# JacdacButton_10.net
KiCad netlist of a schematic drawn in Altium Designer
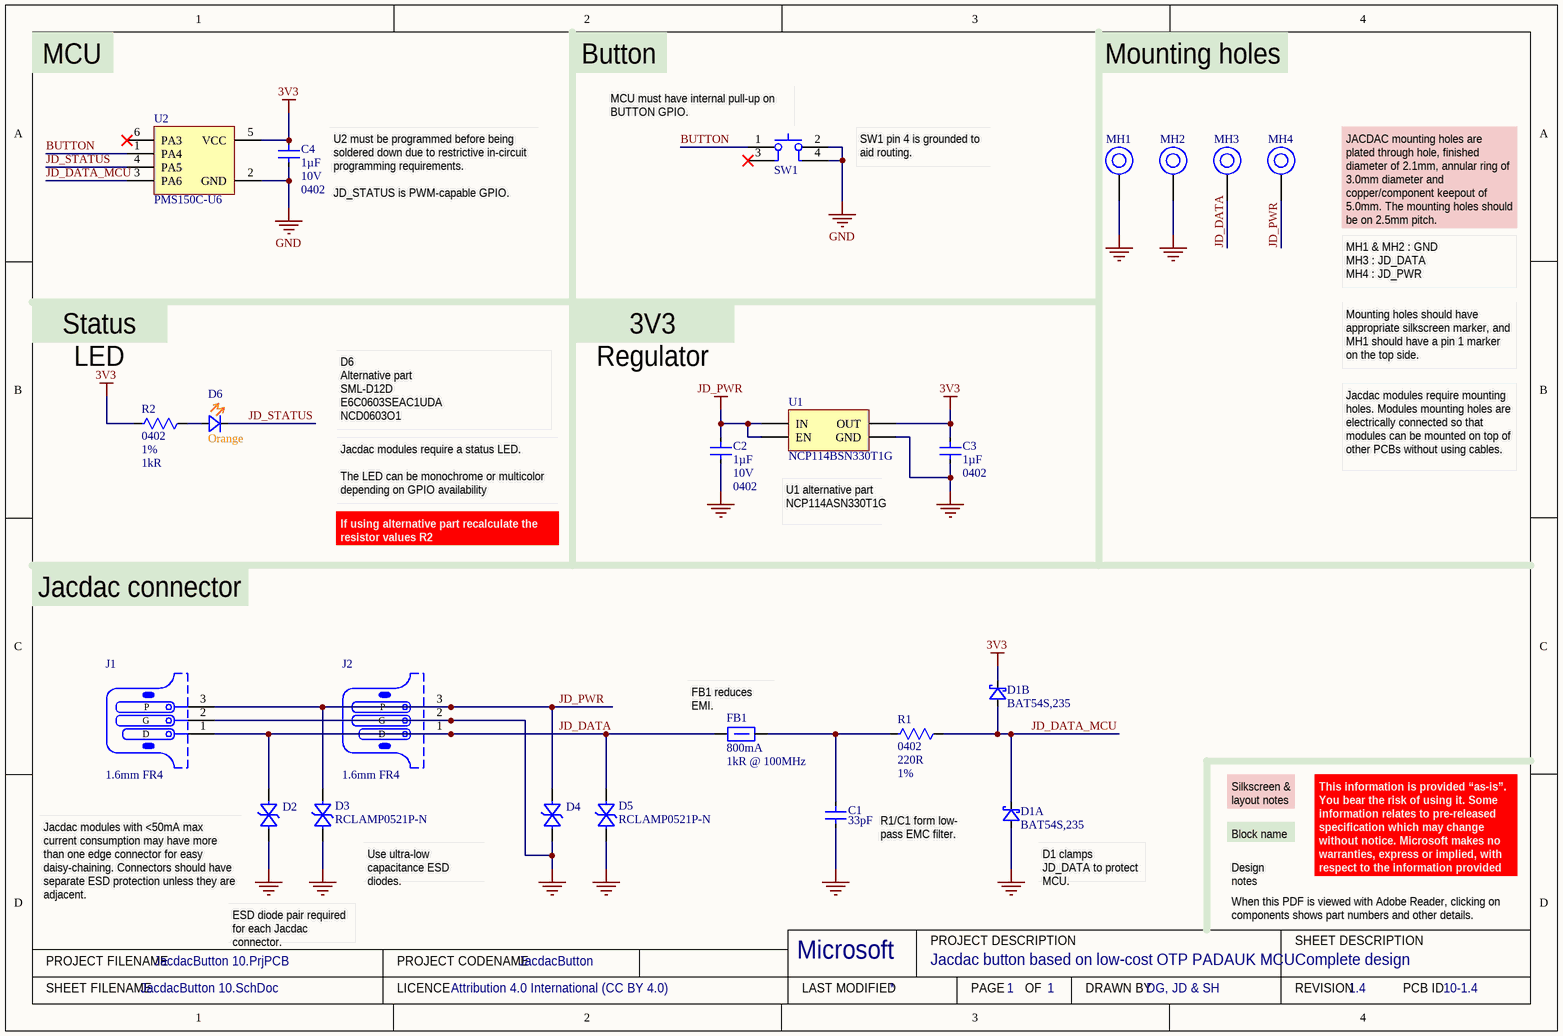
[diagram p0: JacdacButton 10.SchDoc]

(export (version "E")
  (design (tool "Eeschema 10.0.6"))
  (components
    (comp (ref "C1")
      (value "CL05C330JB5NNNC")
      (footprint "C0402_0.55MM - without outline")
      (description "CAP CER 33PF 50V C0G/NP0 0402")
      (fields
        (field (name "MANUFACTURER") "Samsung")
        (field (name "TOLERANCE") "5%")
        (field (name "CAPACITANCE") "33pF")
      )
      (libsource (lib "Samsung") (part "CL05C330JB5NNNC"))
    )
    (comp (ref "C2")
      (value "CL05A105KP5NNNC")
      (footprint "C0402_0.55MM - without outline")
      (description "CAP CER 1UF 10V X5R 0402")
      (fields
        (field (name "MANUFACTURER") "Samsung")
        (field (name "TOLERANCE") "10%")
        (field (name "CAPACITANCE") "1µF")
        (field (name "VOLTAGE RATING") "10V")
        (field (name "CASE CODE (IMPERIAL)") "0402")
        (field (name "CREATED") "DG")
        (field (name "CHECKED") "?")
      )
      (libsource (lib "Samsung") (part "CL05A105KP5NNNC"))
    )
    (comp (ref "C3")
      (value "CL05A105KP5NNNC")
      (footprint "C0402_0.55MM - without outline")
      (description "CAP CER 1UF 10V X5R 0402")
      (fields
        (field (name "MANUFACTURER") "Samsung")
        (field (name "TOLERANCE") "10%")
        (field (name "CAPACITANCE") "1µF")
        (field (name "CASE CODE (IMPERIAL)") "0402")
        (field (name "CREATED") "DG")
        (field (name "CHECKED") "?")
      )
      (libsource (lib "Samsung") (part "CL05A105KP5NNNC"))
    )
    (comp (ref "C4")
      (value "CL05A105KP5NNNC")
      (footprint "C0402_0.55MM - without outline")
      (description "CAP CER 1UF 10V X5R 0402")
      (fields
        (field (name "MANUFACTURER") "Samsung")
        (field (name "TOLERANCE") "10%")
        (field (name "CAPACITANCE") "1µF")
        (field (name "VOLTAGE RATING") "10V")
        (field (name "CASE CODE (IMPERIAL)") "0402")
        (field (name "CREATED") "DG")
        (field (name "CHECKED") "?")
      )
      (libsource (lib "Samsung") (part "CL05A105KP5NNNC"))
    )
    (comp (ref "D1")
      (value "BAT54S")
      (footprint "NXP-BAT54S-TO-236AB - without outline")
      (description "DIODE ARRAY SCHOTTKY 30V SOT23")
      (fields (field (name "MANUFACTURER") "Nexperia") (field (name "MANUFACTURER PART NUMBER") "BAT54S,235"))
      (libsource (lib "NXP") (part "BAT54S"))
    )
    (comp (ref "D2")
      (value "RCLAMP0521P-N")
      (footprint "TVS 0402 - L")
      (description "Bidirectional 5V (Max) 6V 16V 3.5A (8/20us) 0402 TVS RoHS")
      (fields
        (field (name "MANUFACTURER") "Born Semiconductor")
        (field (name "CREATED BY") "D Gakure")
        (field (name "CHECKED BY") "?")
      )
      (libsource (lib "BornSemiconductor") (part "RCLAMP0521P-N"))
    )
    (comp (ref "D3")
      (value "RCLAMP0521P-N")
      (footprint "TVS 0402 - L")
      (description "Bidirectional 5V (Max) 6V 16V 3.5A (8/20us) 0402 TVS RoHS")
      (fields
        (field (name "MANUFACTURER") "Born Semiconductor")
        (field (name "MANUFACTURER PART NUMBER") "RCLAMP0521P-N")
        (field (name "CREATED BY") "D Gakure")
        (field (name "CHECKED BY") "?")
      )
      (libsource (lib "BornSemiconductor") (part "RCLAMP0521P-N"))
    )
    (comp (ref "D4")
      (value "RCLAMP0521P-N")
      (footprint "TVS 0402 - L")
      (description "Bidirectional 5V (Max) 6V 16V 3.5A (8/20us) 0402 TVS RoHS")
      (fields
        (field (name "MANUFACTURER") "Born Semiconductor")
        (field (name "CREATED BY") "D Gakure")
        (field (name "CHECKED BY") "?")
      )
      (libsource (lib "BornSemiconductor") (part "RCLAMP0521P-N"))
    )
    (comp (ref "D5")
      (value "RCLAMP0521P-N")
      (footprint "TVS 0402 - L")
      (description "Bidirectional 5V (Max) 6V 16V 3.5A (8/20us) 0402 TVS RoHS")
      (fields
        (field (name "MANUFACTURER") "Born Semiconductor")
        (field (name "MANUFACTURER PART NUMBER") "RCLAMP0521P-N")
        (field (name "CREATED BY") "D Gakure")
        (field (name "CHECKED BY") "?")
      )
      (libsource (lib "BornSemiconductor") (part "RCLAMP0521P-N"))
    )
    (comp (ref "D6")
      (value "~")
      (footprint "0603 Orange - without outline")
      (description "LED ORANGE DIFFUSED 1608 SMD")
      (fields
        (field (name "MANUFACTURER") "Everlight Elec")
        (field (name "MANUFACTURER PART NUMBER") "19-217/S2C-AQ1R1B/3T")
        (field (name "COLOUR") "Orange")
      )
      (libsource (lib "EverlightElec") (part "19-217/S2C-AQ1R1B/3T"))
    )
    (comp (ref "FB1")
      (value "TDK MPZ1608S102ATA00")
      (footprint "TDK MPZ1608 0.8mm - without outline")
      (description "0603 1k@100MHz 0.8A chip")
      (fields
        (field (name "TOLERANCE") "25%")
        (field (name "MANUFACTURER") "TDK")
        (field (name "CURRENT RATING") "800mA")
        (field (name "IMPEDANCE") "1kR @ 100MHz")
      )
      (libsource (lib "TDK") (part "TDK MPZ1608S102ATA00"))
    )
    (comp (ref "J1")
      (value "3 pin JACDAC edge connector")
      (footprint "JACDAC_EDGE_CONNECTOR_NO_TRACES")
      (description "3 pin Jacdac edge connector 1.27mm pitch")
      (fields
        (field (name "MANUFACTURER PART NUMBER") "JACDAC_EDGE_CONNECTOR")
        (field (name "PCB TYPE") "1.6mm FR4")
        (field (name "CHECKED BY") "?")
        (field (name "CREATED BY") "D. Gakure")
      )
      (libsource (lib "generic-con") (part "Jacdac edge connector"))
    )
    (comp (ref "J2")
      (value "3 pin JACDAC edge connector")
      (footprint "JACDAC_EDGE_CONNECTOR_NO_TRACES")
      (description "3 pin Jacdac edge connector 1.27mm pitch")
      (fields
        (field (name "MANUFACTURER PART NUMBER") "JACDAC_EDGE_CONNECTOR")
        (field (name "PCB TYPE") "1.6mm FR4")
        (field (name "CHECKED BY") "?")
        (field (name "CREATED BY") "D. Gakure")
      )
      (libsource (lib "generic-con") (part "Jacdac edge connector"))
    )
    (comp (ref "MH1")
      (value "MH_5.0MMK_3.0MMC_2.1MMD_PTH")
      (footprint "MH_5.0MMK_3.0MMC_2.1MMD_PTH")
      (description "Mounting Hole 5.0mm keepout, 3.0mm annualar ring and 2.1mm Drill PTH")
      (libsource (lib "generic") (part "MH_5.0MMK_3.0MMC_2.1MMD_PTH"))
    )
    (comp (ref "MH2")
      (value "MH_5.0MMK_3.0MMC_2.1MMD_PTH")
      (footprint "MH_5.0MMK_3.0MMC_2.1MMD_PTH")
      (description "Mounting Hole 5.0mm keepout, 3.0mm annualar ring and 2.1mm Drill PTH")
      (libsource (lib "generic") (part "MH_5.0MMK_3.0MMC_2.1MMD_PTH"))
    )
    (comp (ref "MH3")
      (value "MH_5.0MMK_3.0MMC_2.1MMD_PTH")
      (footprint "MH_5.0MMK_3.0MMC_2.1MMD_PTH")
      (description "Mounting Hole 5.0mm keepout, 3.0mm annualar ring and 2.1mm Drill PTH")
      (libsource (lib "generic") (part "MH_5.0MMK_3.0MMC_2.1MMD_PTH"))
    )
    (comp (ref "MH4")
      (value "MH_5.0MMK_3.0MMC_2.1MMD_PTH")
      (footprint "MH_5.0MMK_3.0MMC_2.1MMD_PTH")
      (description "Mounting Hole 5.0mm keepout, 3.0mm annualar ring and 2.1mm Drill PTH")
      (libsource (lib "generic") (part "MH_5.0MMK_3.0MMC_2.1MMD_PTH"))
    )
    (comp (ref "R1")
      (value "RC0402FR-07220RL")
      (footprint "R0402 - Without outline")
      (description "RES SMD 220 OHM 1% 1/16W 0402")
      (fields
        (field (name "MANUFACTURER") "Yageo")
        (field (name "CASE CODE (IMPERIAL)") "0402")
        (field (name "RESISTANCE") "220R")
        (field (name "TOLERANCE") "1%")
        (field (name "CREATED") "D.G")
        (field (name "CHECKED") "?")
      )
      (libsource (lib "Yageo") (part "RC0402FR-07220RL"))
    )
    (comp (ref "R2")
      (value "RC0402FR-071KL")
      (footprint "R0402 - Without outline")
      (description "RES SMD 1K OHM 1% 1/16W 0402")
      (fields
        (field (name "MANUFACTURER") "Yageo")
        (field (name "CASE CODE (IMPERIAL)") "0402")
        (field (name "TOLERANCE") "1%")
        (field (name "RESISTANCE") "1kR")
        (field (name "CREATED") "D.G")
        (field (name "CHECKED") "?")
      )
      (libsource (lib "Yageo") (part "RC0402FR-071KL"))
    )
    (comp (ref "SW1")
      (value "Tact Wurth 430152050826")
      (footprint "Wurth 430152050836-WIDE")
      (description "6x6mm SPST 0.05A 12VDC SMD 260gf")
      (fields
        (field (name "MANUFACTURER") "Wurth Electronics")
        (field (name "MANUFACTURER PART NUMBER") "430152050826")
      )
      (libsource (lib "Wurth") (part "Tact Wurth 430152050826"))
    )
    (comp (ref "U1")
      (value "LDO 3.3V/300 mA")
      (footprint "ON_SEMI-SOT23-5 - without outline")
      (description "CMOS Low Dropout Regulator (LDO), 300 mA 3.3V, Non-Active Discharge, TSOP5")
      (fields
        (field (name "MANUFACTURER") "ON Semiconductor")
        (field (name "MANUFACTURER PART NUMBER") "NCP114BSN330T1G")
      )
      (libsource (lib "OnSemiconductor") (part "NCP114BSN330T1G"))
    )
    (comp (ref "U2")
      (value "PMS150C")
      (footprint "SOT23-6")
      (description "8bit OTP Type IO Controller")
      (fields (field (name "MANUFACTURER PART NUMBER") "PMS150C-U6") (field (name "MANUFACTURER") "PADAUK"))
      (libsource (lib "PADAUK") (part "PMS150C"))
    )
  )
  (nets
    (net (code "1") (name "/BUTTON") (class "Default")
      (node (ref "SW1") (pin "1") (pinfunction "1_1") (pintype "passive"))
      (node (ref "U2") (pin "1") (pinfunction "PA4_1") (pintype "passive"))
    )
    (net (code "2") (name "/JD_DATA") (class "Default")
      (node (ref "D2") (pin "1") (pinfunction "K_1") (pintype "passive"))
      (node (ref "D5") (pin "1") (pinfunction "K_1") (pintype "passive"))
      (node (ref "FB1") (pin "1") (pinfunction "1_1") (pintype "passive"))
      (node (ref "J1") (pin "1") (pinfunction "D_1") (pintype "passive"))
      (node (ref "J2") (pin "1") (pinfunction "D_1") (pintype "passive"))
      (node (ref "MH3") (pin "1") (pinfunction "1_1") (pintype "passive"))
    )
    (net (code "3") (name "/JD_DATA_MCU") (class "Default")
      (node (ref "D1") (pin "3") (pinfunction "K_3") (pintype "passive"))
      (node (ref "R1") (pin "1") (pinfunction "1_1") (pintype "passive"))
      (node (ref "U2") (pin "3") (pinfunction "PA6_3") (pintype "passive"))
    )
    (net (code "4") (name "/JD_STATUS") (class "Default")
      (node (ref "D6") (pin "1") (pinfunction "K_1") (pintype "passive"))
      (node (ref "U2") (pin "4") (pinfunction "PA5_4") (pintype "passive"))
    )
    (net (code "5") (name "3V3") (class "Default")
      (node (ref "C3") (pin "2") (pinfunction "2_2") (pintype "passive"))
      (node (ref "C4") (pin "2") (pinfunction "2_2") (pintype "passive"))
      (node (ref "D1") (pin "2") (pinfunction "K_2") (pintype "passive"))
      (node (ref "R2") (pin "2") (pinfunction "2_2") (pintype "passive"))
      (node (ref "U1") (pin "5") (pinfunction "OUT_5") (pintype "passive"))
      (node (ref "U2") (pin "5") (pinfunction "VCC_5") (pintype "passive"))
    )
    (net (code "6") (name "GND") (class "Default")
      (node (ref "C1") (pin "1") (pinfunction "1_1") (pintype "passive"))
      (node (ref "C2") (pin "1") (pinfunction "1_1") (pintype "passive"))
      (node (ref "C3") (pin "1") (pinfunction "1_1") (pintype "passive"))
      (node (ref "C4") (pin "1") (pinfunction "1_1") (pintype "passive"))
      (node (ref "D1") (pin "1") (pinfunction "A_1") (pintype "passive"))
      (node (ref "D2") (pin "2") (pinfunction "A_2") (pintype "passive"))
      (node (ref "D3") (pin "2") (pinfunction "A_2") (pintype "passive"))
      (node (ref "D4") (pin "2") (pinfunction "A_2") (pintype "passive"))
      (node (ref "D5") (pin "2") (pinfunction "A_2") (pintype "passive"))
      (node (ref "J1") (pin "2") (pinfunction "G_2") (pintype "passive"))
      (node (ref "J2") (pin "2") (pinfunction "G_2") (pintype "passive"))
      (node (ref "MH1") (pin "1") (pinfunction "1_1") (pintype "passive"))
      (node (ref "MH2") (pin "1") (pinfunction "1_1") (pintype "passive"))
      (node (ref "SW1") (pin "2") (pinfunction "2_2") (pintype "passive"))
      (node (ref "SW1") (pin "4") (pinfunction "4_4") (pintype "passive"))
      (node (ref "U1") (pin "2") (pinfunction "GND_2") (pintype "passive"))
      (node (ref "U2") (pin "2") (pinfunction "GND_2") (pintype "passive"))
    )
    (net (code "7") (name "JD_PWR") (class "Default")
      (node (ref "C2") (pin "2") (pinfunction "2_2") (pintype "passive"))
      (node (ref "D3") (pin "1") (pinfunction "K_1") (pintype "passive"))
      (node (ref "D4") (pin "1") (pinfunction "K_1") (pintype "passive"))
      (node (ref "J1") (pin "3") (pinfunction "P_3") (pintype "passive"))
      (node (ref "J2") (pin "3") (pinfunction "P_3") (pintype "passive"))
      (node (ref "MH4") (pin "1") (pinfunction "1_1") (pintype "passive"))
      (node (ref "U1") (pin "1") (pinfunction "IN_1") (pintype "passive"))
      (node (ref "U1") (pin "3") (pinfunction "EN_3") (pintype "passive"))
    )
    (net (code "8") (name "Net-(C1-Pad2)") (class "Default")
      (node (ref "C1") (pin "2") (pinfunction "2_2") (pintype "passive"))
      (node (ref "FB1") (pin "2") (pinfunction "2_2") (pintype "passive"))
      (node (ref "R1") (pin "2") (pinfunction "2_2") (pintype "passive"))
    )
    (net (code "9") (name "Net-(D6-A)") (class "Default")
      (node (ref "D6") (pin "2") (pinfunction "A_2") (pintype "passive"))
      (node (ref "R2") (pin "1") (pinfunction "1_1") (pintype "passive"))
    )
    (net (code "10") (name "unconnected-(SW1-Pad3)") (class "Default")
      (node (ref "SW1") (pin "3") (pinfunction "3_3") (pintype "passive+no_connect"))
    )
    (net (code "11") (name "unconnected-(U2-PA3-Pad6)") (class "Default")
      (node (ref "U2") (pin "6") (pinfunction "PA3_6") (pintype "passive+no_connect"))
    )
  )
)
